# Ex_Controller_1_USB_Device.net
KiCad netlist of a schematic drawn in EAGLE
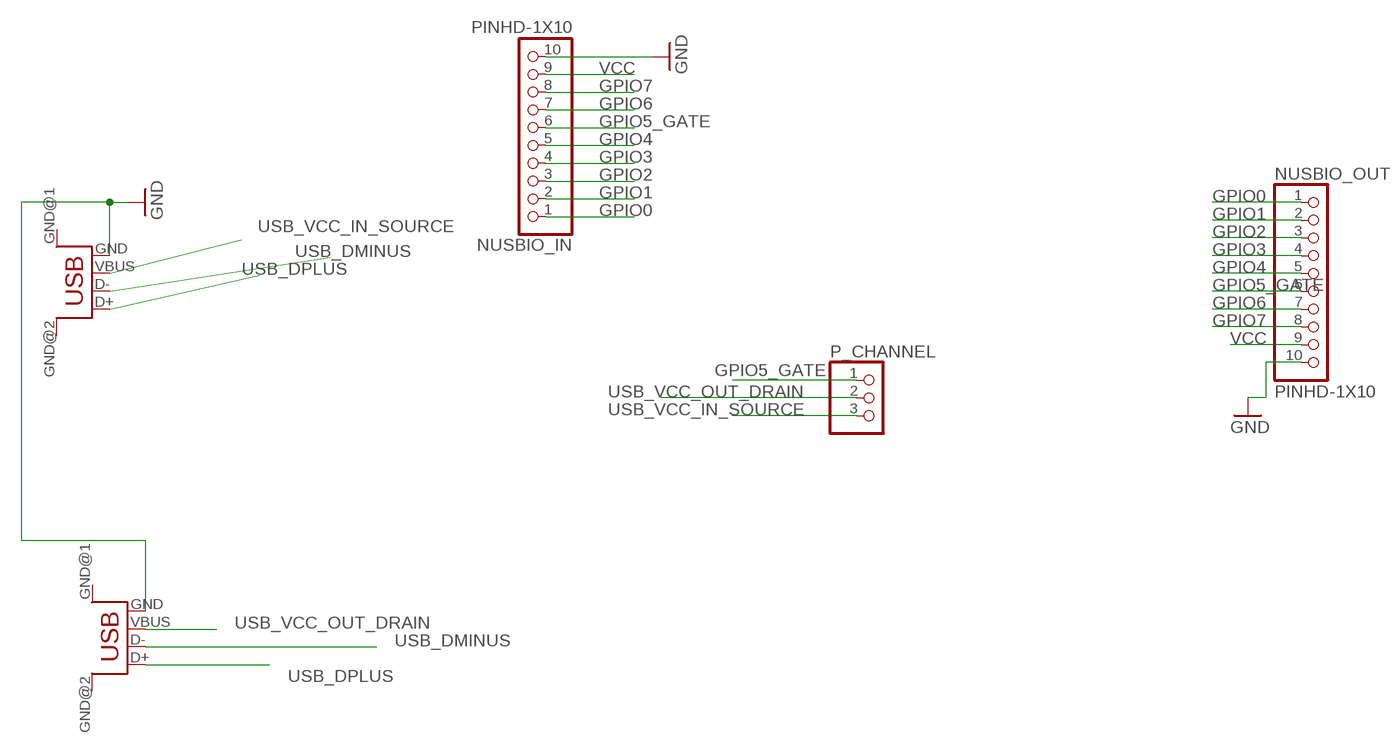
[diagram p0: schematic, sheet 1]

(export (version "E")
  (design (tool "Eeschema 10.0.6"))
  (components
    (comp (ref "NUSBIO_IN")
      (value "PINHD-1X10")
      (footprint "eagle-import:1X10-BIG")
      (libsource (lib "eagle-import") (part "PINHD-1X10"))
    )
    (comp (ref "NUSBIO_OUT")
      (value "PINHD-1X10")
      (footprint "eagle-import:1X10-BIG")
      (libsource (lib "eagle-import") (part "PINHD-1X10"))
    )
    (comp (ref "P_CHANNEL")
      (value "PINHD-1X3")
      (footprint "eagle-import:1X03")
      (libsource (lib "eagle-import") (part "PINHD-1X3"))
    )
    (comp (ref "USB_DEV_INPUT")
      (value "USB")
      (footprint "eagle-import:USB-FEMALE-A-PTH")
      (libsource (lib "eagle-import") (part "USB"))
    )
    (comp (ref "USB_DEV_OUTPUT")
      (value "USB")
      (footprint "eagle-import:USB-FEMALE-A-PTH")
      (libsource (lib "eagle-import") (part "USB"))
    )
  )
  (nets
    (net (code "1") (name "/GPIO0") (class "Default")
      (node (ref "NUSBIO_IN") (pin "1") (pinfunction "1_1") (pintype "passive"))
      (node (ref "NUSBIO_OUT") (pin "1") (pinfunction "1_1") (pintype "passive"))
    )
    (net (code "2") (name "/GPIO1") (class "Default")
      (node (ref "NUSBIO_IN") (pin "2") (pinfunction "2_2") (pintype "passive"))
      (node (ref "NUSBIO_OUT") (pin "2") (pinfunction "2_2") (pintype "passive"))
    )
    (net (code "3") (name "/GPIO2") (class "Default")
      (node (ref "NUSBIO_IN") (pin "3") (pinfunction "3_3") (pintype "passive"))
      (node (ref "NUSBIO_OUT") (pin "3") (pinfunction "3_3") (pintype "passive"))
    )
    (net (code "4") (name "/GPIO3") (class "Default")
      (node (ref "NUSBIO_IN") (pin "4") (pinfunction "4_4") (pintype "passive"))
      (node (ref "NUSBIO_OUT") (pin "4") (pinfunction "4_4") (pintype "passive"))
    )
    (net (code "5") (name "/GPIO4") (class "Default")
      (node (ref "NUSBIO_IN") (pin "5") (pinfunction "5_5") (pintype "passive"))
      (node (ref "NUSBIO_OUT") (pin "5") (pinfunction "5_5") (pintype "passive"))
    )
    (net (code "6") (name "/GPIO5_GATE") (class "Default")
      (node (ref "NUSBIO_IN") (pin "6") (pinfunction "6_6") (pintype "passive"))
      (node (ref "NUSBIO_OUT") (pin "6") (pinfunction "6_6") (pintype "passive"))
      (node (ref "P_CHANNEL") (pin "1") (pinfunction "1_1") (pintype "passive"))
    )
    (net (code "7") (name "/GPIO6") (class "Default")
      (node (ref "NUSBIO_IN") (pin "7") (pinfunction "7_7") (pintype "passive"))
      (node (ref "NUSBIO_OUT") (pin "7") (pinfunction "7_7") (pintype "passive"))
    )
    (net (code "8") (name "/GPIO7") (class "Default")
      (node (ref "NUSBIO_IN") (pin "8") (pinfunction "8_8") (pintype "passive"))
      (node (ref "NUSBIO_OUT") (pin "8") (pinfunction "8_8") (pintype "passive"))
    )
    (net (code "9") (name "/USB_DMINUS") (class "Default")
      (node (ref "USB_DEV_INPUT") (pin "D-") (pinfunction "D-_D-") (pintype "bidirectional"))
      (node (ref "USB_DEV_OUTPUT") (pin "D-") (pinfunction "D-_D-") (pintype "bidirectional"))
    )
    (net (code "10") (name "/USB_DPLUS") (class "Default")
      (node (ref "USB_DEV_INPUT") (pin "D+") (pinfunction "D+_D+") (pintype "bidirectional"))
      (node (ref "USB_DEV_OUTPUT") (pin "D+") (pinfunction "D+_D+") (pintype "bidirectional"))
    )
    (net (code "11") (name "/USB_VCC_IN_SOURCE") (class "Default")
      (node (ref "P_CHANNEL") (pin "3") (pinfunction "3_3") (pintype "passive"))
      (node (ref "USB_DEV_INPUT") (pin "VBUS") (pinfunction "VBUS_VBUS") (pintype "bidirectional"))
    )
    (net (code "12") (name "/USB_VCC_OUT_DRAIN") (class "Default")
      (node (ref "P_CHANNEL") (pin "2") (pinfunction "2_2") (pintype "passive"))
      (node (ref "USB_DEV_OUTPUT") (pin "VBUS") (pinfunction "VBUS_VBUS") (pintype "bidirectional"))
    )
    (net (code "13") (name "/VCC") (class "Default")
      (node (ref "NUSBIO_IN") (pin "9") (pinfunction "9_9") (pintype "passive"))
      (node (ref "NUSBIO_OUT") (pin "9") (pinfunction "9_9") (pintype "passive"))
    )
    (net (code "14") (name "GND") (class "Default")
      (node (ref "NUSBIO_IN") (pin "10") (pinfunction "10_10") (pintype "passive"))
      (node (ref "NUSBIO_OUT") (pin "10") (pinfunction "10_10") (pintype "passive"))
      (node (ref "USB_DEV_INPUT") (pin "GND") (pinfunction "GND_GND") (pintype "bidirectional"))
      (node (ref "USB_DEV_OUTPUT") (pin "GND") (pinfunction "GND_GND") (pintype "bidirectional"))
    )
    (net (code "15") (name "unconnected-(USB_DEV_INPUT-GND-PadGND@1)") (class "Default")
      (node (ref "USB_DEV_INPUT") (pin "GND@1") (pinfunction "GND_GND@1") (pintype "bidirectional"))
    )
    (net (code "16") (name "unconnected-(USB_DEV_INPUT-GND-PadGND@2)") (class "Default")
      (node (ref "USB_DEV_INPUT") (pin "GND@2") (pinfunction "GND_GND@2") (pintype "bidirectional"))
    )
    (net (code "17") (name "unconnected-(USB_DEV_OUTPUT-GND-PadGND@1)") (class "Default")
      (node (ref "USB_DEV_OUTPUT") (pin "GND@1") (pinfunction "GND_GND@1") (pintype "bidirectional"))
    )
    (net (code "18") (name "unconnected-(USB_DEV_OUTPUT-GND-PadGND@2)") (class "Default")
      (node (ref "USB_DEV_OUTPUT") (pin "GND@2") (pinfunction "GND_GND@2") (pintype "bidirectional"))
    )
  )
)
